# 09_CONNECTOR.net
KiCad netlist of a schematic drawn in Altium Designer
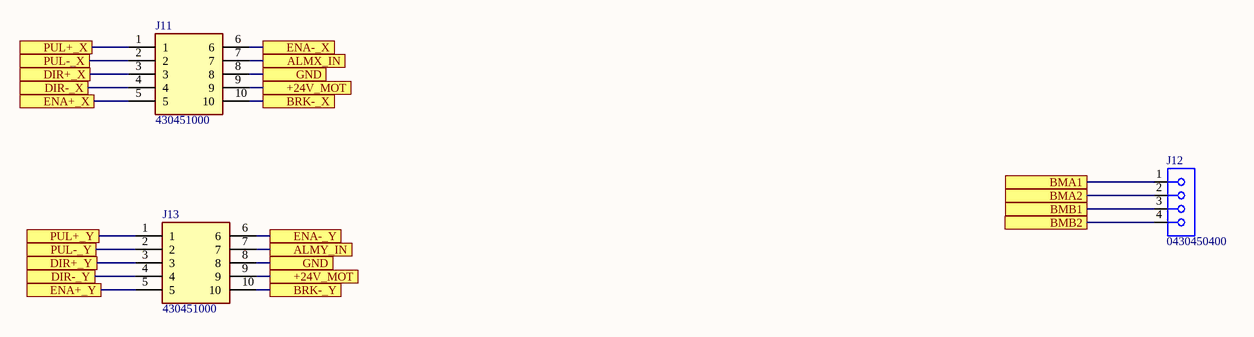
[diagram p0: 09_CONNECTOR.SchDoc]

(export (version "E")
  (design (tool "Eeschema 10.0.6"))
  (components
    (comp (ref "J11")
      (value "430451000")
      (footprint "SamacSys:430451010")
      (description "Connector")
      (libsource (lib "*") (part "430451000"))
    )
    (comp (ref "J12")
      (value "0430450400")
      (footprint "CONN_SD-43045-001_04_MOL")
      (description "Connector Header Through Hole, Right Angle 4 position 0.118\" (3.00mm)")
      (libsource (lib "HW_ADHERENT_SYSCTRL_R1_L1") (part "0430450400"))
    )
    (comp (ref "J13")
      (value "430451000")
      (footprint "SamacSys:430451010")
      (description "Connector")
      (libsource (lib "*") (part "430451000"))
    )
  )
  (nets
    (net (code "1") (name "/+24V_MOT") (class "Default")
      (node (ref "J11") (pin "9") (pinfunction "9_9") (pintype "passive"))
      (node (ref "J13") (pin "9") (pinfunction "9_9") (pintype "passive"))
    )
    (net (code "2") (name "/ALMX_IN") (class "Default")
      (node (ref "J11") (pin "7") (pinfunction "7_7") (pintype "passive"))
    )
    (net (code "3") (name "/ALMY_IN") (class "Default")
      (node (ref "J13") (pin "7") (pinfunction "7_7") (pintype "passive"))
    )
    (net (code "4") (name "/BMA1") (class "Default")
      (node (ref "J12") (pin "1") (pinfunction "1_1") (pintype "passive"))
    )
    (net (code "5") (name "/BMA2") (class "Default")
      (node (ref "J12") (pin "2") (pinfunction "2_2") (pintype "passive"))
    )
    (net (code "6") (name "/BMB1") (class "Default")
      (node (ref "J12") (pin "3") (pinfunction "3_3") (pintype "passive"))
    )
    (net (code "7") (name "/BMB2") (class "Default")
      (node (ref "J12") (pin "4") (pinfunction "4_4") (pintype "passive"))
    )
    (net (code "8") (name "/BRK-_X") (class "Default")
      (node (ref "J11") (pin "10") (pinfunction "10_10") (pintype "passive"))
    )
    (net (code "9") (name "/BRK-_Y") (class "Default")
      (node (ref "J13") (pin "10") (pinfunction "10_10") (pintype "passive"))
    )
    (net (code "10") (name "/DIR+_X") (class "Default")
      (node (ref "J11") (pin "3") (pinfunction "3_3") (pintype "passive"))
    )
    (net (code "11") (name "/DIR+_Y") (class "Default")
      (node (ref "J13") (pin "3") (pinfunction "3_3") (pintype "passive"))
    )
    (net (code "12") (name "/DIR-_X") (class "Default")
      (node (ref "J11") (pin "4") (pinfunction "4_4") (pintype "passive"))
    )
    (net (code "13") (name "/DIR-_Y") (class "Default")
      (node (ref "J13") (pin "4") (pinfunction "4_4") (pintype "passive"))
    )
    (net (code "14") (name "/ENA+_X") (class "Default")
      (node (ref "J11") (pin "5") (pinfunction "5_5") (pintype "passive"))
    )
    (net (code "15") (name "/ENA+_Y") (class "Default")
      (node (ref "J13") (pin "5") (pinfunction "5_5") (pintype "passive"))
    )
    (net (code "16") (name "/ENA-_X") (class "Default")
      (node (ref "J11") (pin "6") (pinfunction "6_6") (pintype "passive"))
    )
    (net (code "17") (name "/ENA-_Y") (class "Default")
      (node (ref "J13") (pin "6") (pinfunction "6_6") (pintype "passive"))
    )
    (net (code "18") (name "/GND") (class "Default")
      (node (ref "J11") (pin "8") (pinfunction "8_8") (pintype "passive"))
      (node (ref "J13") (pin "8") (pinfunction "8_8") (pintype "passive"))
    )
    (net (code "19") (name "/PUL+_X") (class "Default")
      (node (ref "J11") (pin "1") (pinfunction "1_1") (pintype "passive"))
    )
    (net (code "20") (name "/PUL+_Y") (class "Default")
      (node (ref "J13") (pin "1") (pinfunction "1_1") (pintype "passive"))
    )
    (net (code "21") (name "/PUL-_X") (class "Default")
      (node (ref "J11") (pin "2") (pinfunction "2_2") (pintype "passive"))
    )
    (net (code "22") (name "/PUL-_Y") (class "Default")
      (node (ref "J13") (pin "2") (pinfunction "2_2") (pintype "passive"))
    )
  )
)
